# PERIPHERAL_CON.net
KiCad netlist of a schematic drawn in Altium Designer
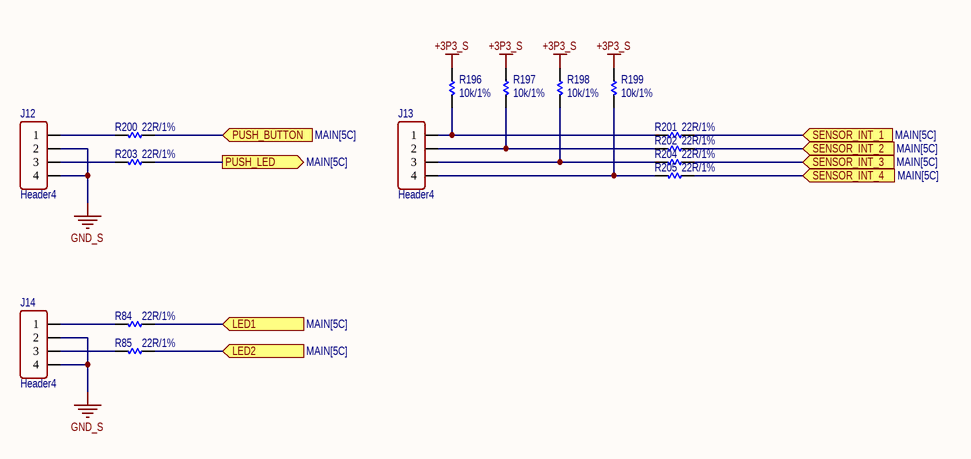
[diagram p0: PERIPHERAL_CON.SchDoc]

(export (version "E")
  (design (tool "Eeschema 10.0.6"))
  (components
    (comp (ref "J12")
      (value "Header4")
      (footprint "XH2.54-4-DIP")
      (description "Connector 4")
      (fields
        (field (name "MANUFACTURER") "Würth Elektronik eiSos GmbH")
        (field (name "PARTNO") "613002143121")
        (field (name "CREATED BY") "Karrer Zheng")
      )
      (libsource (lib "Library") (part "Header4"))
    )
    (comp (ref "J13")
      (value "Header4")
      (footprint "XH2.54-4-DIP")
      (description "Connector 4")
      (fields
        (field (name "MANUFACTURER") "Würth Elektronik eiSos GmbH")
        (field (name "PARTNO") "613002143121")
        (field (name "CREATED BY") "Karrer Zheng")
      )
      (libsource (lib "Library") (part "Header4"))
    )
    (comp (ref "J14")
      (value "Header4")
      (footprint "XH2.54-4-DIP")
      (description "Connector 4")
      (fields
        (field (name "MANUFACTURER") "Würth Elektronik eiSos GmbH")
        (field (name "PARTNO") "613002143121")
        (field (name "CREATED BY") "Karrer Zheng")
      )
      (libsource (lib "Library") (part "Header4"))
    )
    (comp (ref "R84")
      (value "22R/1%")
      (footprint "RES-SMD-0603")
      (description "ERJ-3EKF22R0V")
      (libsource (lib "Library") (part "Res-SMD"))
    )
    (comp (ref "R85")
      (value "22R/1%")
      (footprint "RES-SMD-0603")
      (description "ERJ-3EKF22R0V")
      (libsource (lib "Library") (part "Res-SMD"))
    )
    (comp (ref "R196")
      (value "10k/1%")
      (footprint "RES-SMD-0603")
      (description "ERJ-3EKF1002V")
      (fields
        (field (name "MANUFACTURER") "Generic Components")
        (field (name "PUBLISHER") "Altium Hobart Technology Centre")
      )
      (libsource (lib "Library") (part "Res-SMD"))
    )
    (comp (ref "R197")
      (value "10k/1%")
      (footprint "RES-SMD-0603")
      (description "ERJ-3EKF1002V")
      (fields
        (field (name "MANUFACTURER") "Generic Components")
        (field (name "PUBLISHER") "Altium Hobart Technology Centre")
      )
      (libsource (lib "Library") (part "Res-SMD"))
    )
    (comp (ref "R198")
      (value "10k/1%")
      (footprint "RES-SMD-0603")
      (description "ERJ-3EKF1002V")
      (fields
        (field (name "MANUFACTURER") "Generic Components")
        (field (name "PUBLISHER") "Altium Hobart Technology Centre")
      )
      (libsource (lib "Library") (part "Res-SMD"))
    )
    (comp (ref "R199")
      (value "10k/1%")
      (footprint "RES-SMD-0603")
      (description "ERJ-3EKF1002V")
      (fields
        (field (name "MANUFACTURER") "Generic Components")
        (field (name "PUBLISHER") "Altium Hobart Technology Centre")
      )
      (libsource (lib "Library") (part "Res-SMD"))
    )
    (comp (ref "R200")
      (value "22R/1%")
      (footprint "RES-SMD-0603")
      (description "ERJ-3EKF22R0V")
      (libsource (lib "Library") (part "Res-SMD"))
    )
    (comp (ref "R201")
      (value "22R/1%")
      (footprint "RES-SMD-0603")
      (description "ERJ-3EKF22R0V")
      (libsource (lib "Library") (part "Res-SMD"))
    )
    (comp (ref "R202")
      (value "22R/1%")
      (footprint "RES-SMD-0603")
      (description "ERJ-3EKF22R0V")
      (libsource (lib "Library") (part "Res-SMD"))
    )
    (comp (ref "R203")
      (value "22R/1%")
      (footprint "RES-SMD-0603")
      (description "ERJ-3EKF22R0V")
      (libsource (lib "Library") (part "Res-SMD"))
    )
    (comp (ref "R204")
      (value "22R/1%")
      (footprint "RES-SMD-0603")
      (description "ERJ-3EKF22R0V")
      (libsource (lib "Library") (part "Res-SMD"))
    )
    (comp (ref "R205")
      (value "22R/1%")
      (footprint "RES-SMD-0603")
      (description "ERJ-3EKF22R0V")
      (libsource (lib "Library") (part "Res-SMD"))
    )
  )
  (nets
    (net (code "1") (name "+3P3_S") (class "Default")
      (node (ref "R196") (pin "1") (pinfunction "1_1") (pintype "passive"))
      (node (ref "R197") (pin "1") (pinfunction "1_1") (pintype "passive"))
      (node (ref "R198") (pin "1") (pinfunction "1_1") (pintype "passive"))
      (node (ref "R199") (pin "1") (pinfunction "1_1") (pintype "passive"))
    )
    (net (code "2") (name "/LED1") (class "Default")
      (node (ref "R84") (pin "1") (pinfunction "1_1") (pintype "passive"))
    )
    (net (code "3") (name "/LED2") (class "Default")
      (node (ref "R85") (pin "1") (pinfunction "1_1") (pintype "passive"))
    )
    (net (code "4") (name "/PUSH_BUTTON") (class "Default")
      (node (ref "R200") (pin "1") (pinfunction "1_1") (pintype "passive"))
    )
    (net (code "5") (name "/PUSH_LED") (class "Default")
      (node (ref "R203") (pin "1") (pinfunction "1_1") (pintype "passive"))
    )
    (net (code "6") (name "/SENSOR_INT_1") (class "Default")
      (node (ref "R201") (pin "1") (pinfunction "1_1") (pintype "passive"))
    )
    (net (code "7") (name "/SENSOR_INT_2") (class "Default")
      (node (ref "R202") (pin "1") (pinfunction "1_1") (pintype "passive"))
    )
    (net (code "8") (name "/SENSOR_INT_3") (class "Default")
      (node (ref "R204") (pin "1") (pinfunction "1_1") (pintype "passive"))
    )
    (net (code "9") (name "/SENSOR_INT_4") (class "Default")
      (node (ref "R205") (pin "1") (pinfunction "1_1") (pintype "passive"))
    )
    (net (code "10") (name "GND_S") (class "Default")
      (node (ref "J12") (pin "2") (pinfunction "2_2") (pintype "passive"))
      (node (ref "J12") (pin "4") (pinfunction "4_4") (pintype "passive"))
      (node (ref "J14") (pin "2") (pinfunction "2_2") (pintype "passive"))
      (node (ref "J14") (pin "4") (pinfunction "4_4") (pintype "passive"))
    )
    (net (code "11") (name "Net-(J12-Pad1)") (class "Default")
      (node (ref "J12") (pin "1") (pinfunction "1_1") (pintype "passive"))
      (node (ref "R200") (pin "2") (pinfunction "2_2") (pintype "passive"))
    )
    (net (code "12") (name "Net-(J12-Pad3)") (class "Default")
      (node (ref "J12") (pin "3") (pinfunction "3_3") (pintype "passive"))
      (node (ref "R203") (pin "2") (pinfunction "2_2") (pintype "passive"))
    )
    (net (code "13") (name "Net-(J13-Pad1)") (class "Default")
      (node (ref "J13") (pin "1") (pinfunction "1_1") (pintype "passive"))
      (node (ref "R196") (pin "2") (pinfunction "2_2") (pintype "passive"))
      (node (ref "R201") (pin "2") (pinfunction "2_2") (pintype "passive"))
    )
    (net (code "14") (name "Net-(J13-Pad2)") (class "Default")
      (node (ref "J13") (pin "2") (pinfunction "2_2") (pintype "passive"))
      (node (ref "R197") (pin "2") (pinfunction "2_2") (pintype "passive"))
      (node (ref "R202") (pin "2") (pinfunction "2_2") (pintype "passive"))
    )
    (net (code "15") (name "Net-(J13-Pad3)") (class "Default")
      (node (ref "J13") (pin "3") (pinfunction "3_3") (pintype "passive"))
      (node (ref "R198") (pin "2") (pinfunction "2_2") (pintype "passive"))
      (node (ref "R204") (pin "2") (pinfunction "2_2") (pintype "passive"))
    )
    (net (code "16") (name "Net-(J13-Pad4)") (class "Default")
      (node (ref "J13") (pin "4") (pinfunction "4_4") (pintype "passive"))
      (node (ref "R199") (pin "2") (pinfunction "2_2") (pintype "passive"))
      (node (ref "R205") (pin "2") (pinfunction "2_2") (pintype "passive"))
    )
    (net (code "17") (name "Net-(J14-Pad1)") (class "Default")
      (node (ref "J14") (pin "1") (pinfunction "1_1") (pintype "passive"))
      (node (ref "R84") (pin "2") (pinfunction "2_2") (pintype "passive"))
    )
    (net (code "18") (name "Net-(J14-Pad3)") (class "Default")
      (node (ref "J14") (pin "3") (pinfunction "3_3") (pintype "passive"))
      (node (ref "R85") (pin "2") (pinfunction "2_2") (pintype "passive"))
    )
  )
)
